# SwitchPanel.net
KiCad netlist of a schematic drawn in EAGLE
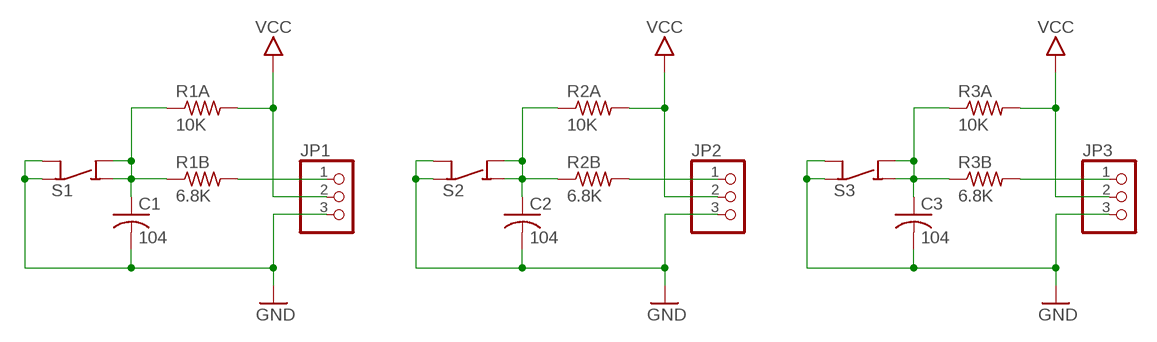
[diagram p0: schematic, sheet 1]

(export (version "E")
  (design (tool "Eeschema 10.0.6"))
  (components
    (comp (ref "C1")
      (value "104")
      (footprint "eagle-import:C075")
      (libsource (lib "eagle-import") (part "C-075PTH"))
    )
    (comp (ref "C2")
      (value "104")
      (footprint "eagle-import:C075")
      (libsource (lib "eagle-import") (part "C-075PTH"))
    )
    (comp (ref "C3")
      (value "104")
      (footprint "eagle-import:C075")
      (libsource (lib "eagle-import") (part "C-075PTH"))
    )
    (comp (ref "JP1")
      (value "PINHD-1X03_2.54-90°-S")
      (footprint "eagle-import:1X03_90-S")
      (libsource (lib "eagle-import") (part "PINHD-1X03_2.54-90°-S"))
    )
    (comp (ref "JP2")
      (value "PINHD-1X03_2.54-90°-S")
      (footprint "eagle-import:1X03_90-S")
      (libsource (lib "eagle-import") (part "PINHD-1X03_2.54-90°-S"))
    )
    (comp (ref "JP3")
      (value "PINHD-1X03_2.54-90°-S")
      (footprint "eagle-import:1X03_90-S")
      (libsource (lib "eagle-import") (part "PINHD-1X03_2.54-90°-S"))
    )
    (comp (ref "R1A")
      (value "10K")
      (footprint "eagle-import:0207_7")
      (libsource (lib "eagle-import") (part "R0207-PTH"))
    )
    (comp (ref "R1B")
      (value "6.8K")
      (footprint "eagle-import:0207_7")
      (libsource (lib "eagle-import") (part "R0207-PTH"))
    )
    (comp (ref "R2A")
      (value "10K")
      (footprint "eagle-import:0207_7")
      (libsource (lib "eagle-import") (part "R0207-PTH"))
    )
    (comp (ref "R2B")
      (value "6.8K")
      (footprint "eagle-import:0207_7")
      (libsource (lib "eagle-import") (part "R0207-PTH"))
    )
    (comp (ref "R3A")
      (value "10K")
      (footprint "eagle-import:0207_7")
      (libsource (lib "eagle-import") (part "R0207-PTH"))
    )
    (comp (ref "R3B")
      (value "6.8K")
      (footprint "eagle-import:0207_7")
      (libsource (lib "eagle-import") (part "R0207-PTH"))
    )
    (comp (ref "S1")
      (value "SPST412MM")
      (footprint "eagle-import:12MMTACTILE_4PIN")
      (libsource (lib "eagle-import") (part "SPST412MM"))
    )
    (comp (ref "S2")
      (value "SPST412MM")
      (footprint "eagle-import:12MMTACTILE_4PIN")
      (libsource (lib "eagle-import") (part "SPST412MM"))
    )
    (comp (ref "S3")
      (value "SPST412MM")
      (footprint "eagle-import:12MMTACTILE_4PIN")
      (libsource (lib "eagle-import") (part "SPST412MM"))
    )
  )
  (nets
    (net (code "1") (name "GND") (class "Default")
      (node (ref "C1") (pin "2") (pinfunction "-_2") (pintype "passive"))
      (node (ref "C2") (pin "2") (pinfunction "-_2") (pintype "passive"))
      (node (ref "C3") (pin "2") (pinfunction "-_2") (pintype "passive"))
      (node (ref "JP1") (pin "3") (pinfunction "3_3") (pintype "passive"))
      (node (ref "JP2") (pin "3") (pinfunction "3_3") (pintype "passive"))
      (node (ref "JP3") (pin "3") (pinfunction "3_3") (pintype "passive"))
      (node (ref "S1") (pin "P1A") (pinfunction "COM_P1A") (pintype "passive"))
      (node (ref "S1") (pin "P1B") (pinfunction "COM_P1B") (pintype "passive"))
      (node (ref "S2") (pin "P1A") (pinfunction "COM_P1A") (pintype "passive"))
      (node (ref "S2") (pin "P1B") (pinfunction "COM_P1B") (pintype "passive"))
      (node (ref "S3") (pin "P1A") (pinfunction "COM_P1A") (pintype "passive"))
      (node (ref "S3") (pin "P1B") (pinfunction "COM_P1B") (pintype "passive"))
    )
    (net (code "2") (name "Net-(C1-+)") (class "Default")
      (node (ref "C1") (pin "1") (pinfunction "+_1") (pintype "passive"))
      (node (ref "R1A") (pin "1") (pinfunction "1_1") (pintype "passive"))
      (node (ref "R1B") (pin "1") (pinfunction "1_1") (pintype "passive"))
      (node (ref "S1") (pin "P2A") (pinfunction "NO_P2A") (pintype "passive"))
      (node (ref "S1") (pin "P2B") (pinfunction "NO_P2B") (pintype "passive"))
    )
    (net (code "3") (name "Net-(C2-+)") (class "Default")
      (node (ref "C2") (pin "1") (pinfunction "+_1") (pintype "passive"))
      (node (ref "R2A") (pin "1") (pinfunction "1_1") (pintype "passive"))
      (node (ref "R2B") (pin "1") (pinfunction "1_1") (pintype "passive"))
      (node (ref "S2") (pin "P2A") (pinfunction "NO_P2A") (pintype "passive"))
      (node (ref "S2") (pin "P2B") (pinfunction "NO_P2B") (pintype "passive"))
    )
    (net (code "4") (name "Net-(C3-+)") (class "Default")
      (node (ref "C3") (pin "1") (pinfunction "+_1") (pintype "passive"))
      (node (ref "R3A") (pin "1") (pinfunction "1_1") (pintype "passive"))
      (node (ref "R3B") (pin "1") (pinfunction "1_1") (pintype "passive"))
      (node (ref "S3") (pin "P2A") (pinfunction "NO_P2A") (pintype "passive"))
      (node (ref "S3") (pin "P2B") (pinfunction "NO_P2B") (pintype "passive"))
    )
    (net (code "5") (name "Net-(JP1-Pad1)") (class "Default")
      (node (ref "JP1") (pin "1") (pinfunction "1_1") (pintype "passive"))
      (node (ref "R1B") (pin "2") (pinfunction "2_2") (pintype "passive"))
    )
    (net (code "6") (name "Net-(JP2-Pad1)") (class "Default")
      (node (ref "JP2") (pin "1") (pinfunction "1_1") (pintype "passive"))
      (node (ref "R2B") (pin "2") (pinfunction "2_2") (pintype "passive"))
    )
    (net (code "7") (name "Net-(JP3-Pad1)") (class "Default")
      (node (ref "JP3") (pin "1") (pinfunction "1_1") (pintype "passive"))
      (node (ref "R3B") (pin "2") (pinfunction "2_2") (pintype "passive"))
    )
    (net (code "8") (name "VCC") (class "Default")
      (node (ref "JP1") (pin "2") (pinfunction "2_2") (pintype "passive"))
      (node (ref "JP2") (pin "2") (pinfunction "2_2") (pintype "passive"))
      (node (ref "JP3") (pin "2") (pinfunction "2_2") (pintype "passive"))
      (node (ref "R1A") (pin "2") (pinfunction "2_2") (pintype "passive"))
      (node (ref "R2A") (pin "2") (pinfunction "2_2") (pintype "passive"))
      (node (ref "R3A") (pin "2") (pinfunction "2_2") (pintype "passive"))
    )
  )
)
